# SCH_TWINKLING_CHRISMATIS_LIGHT_2023-04-2.net
KiCad netlist of a schematic drawn in EasyEDA
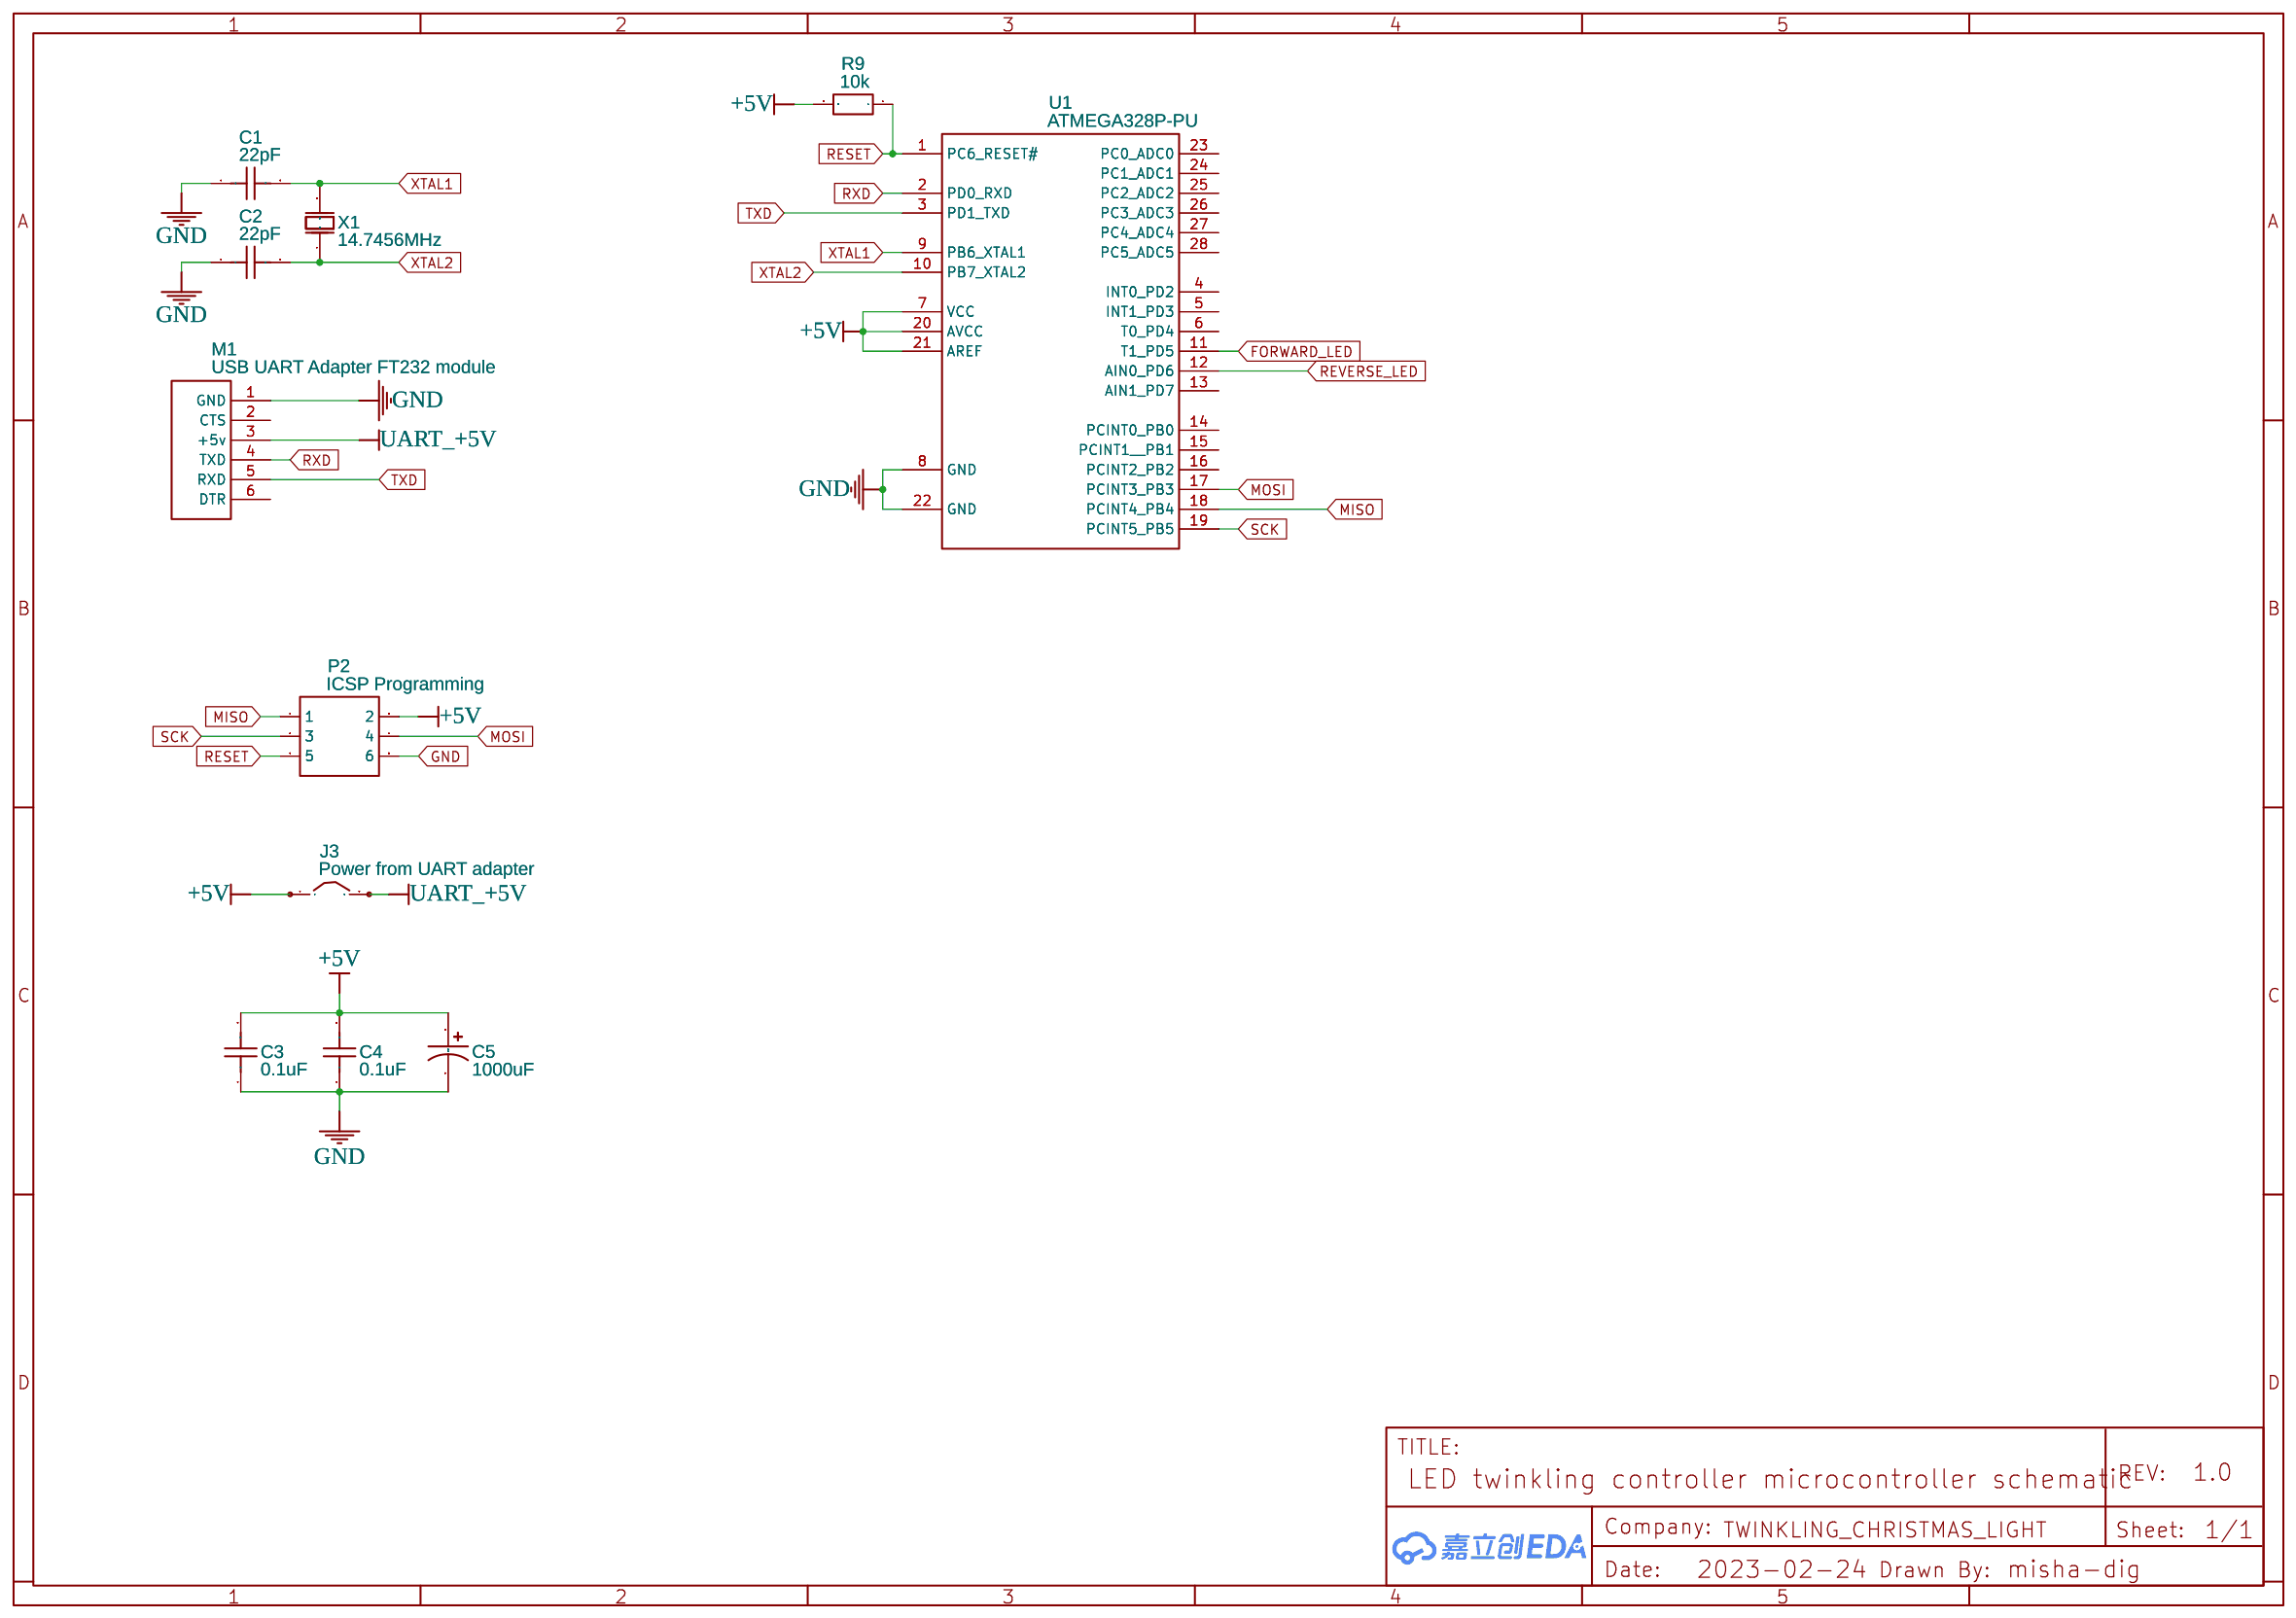
[diagram p0: MAIN_SCHEMATIC_TWINKLING_CHRISTMAS_LIGHT]
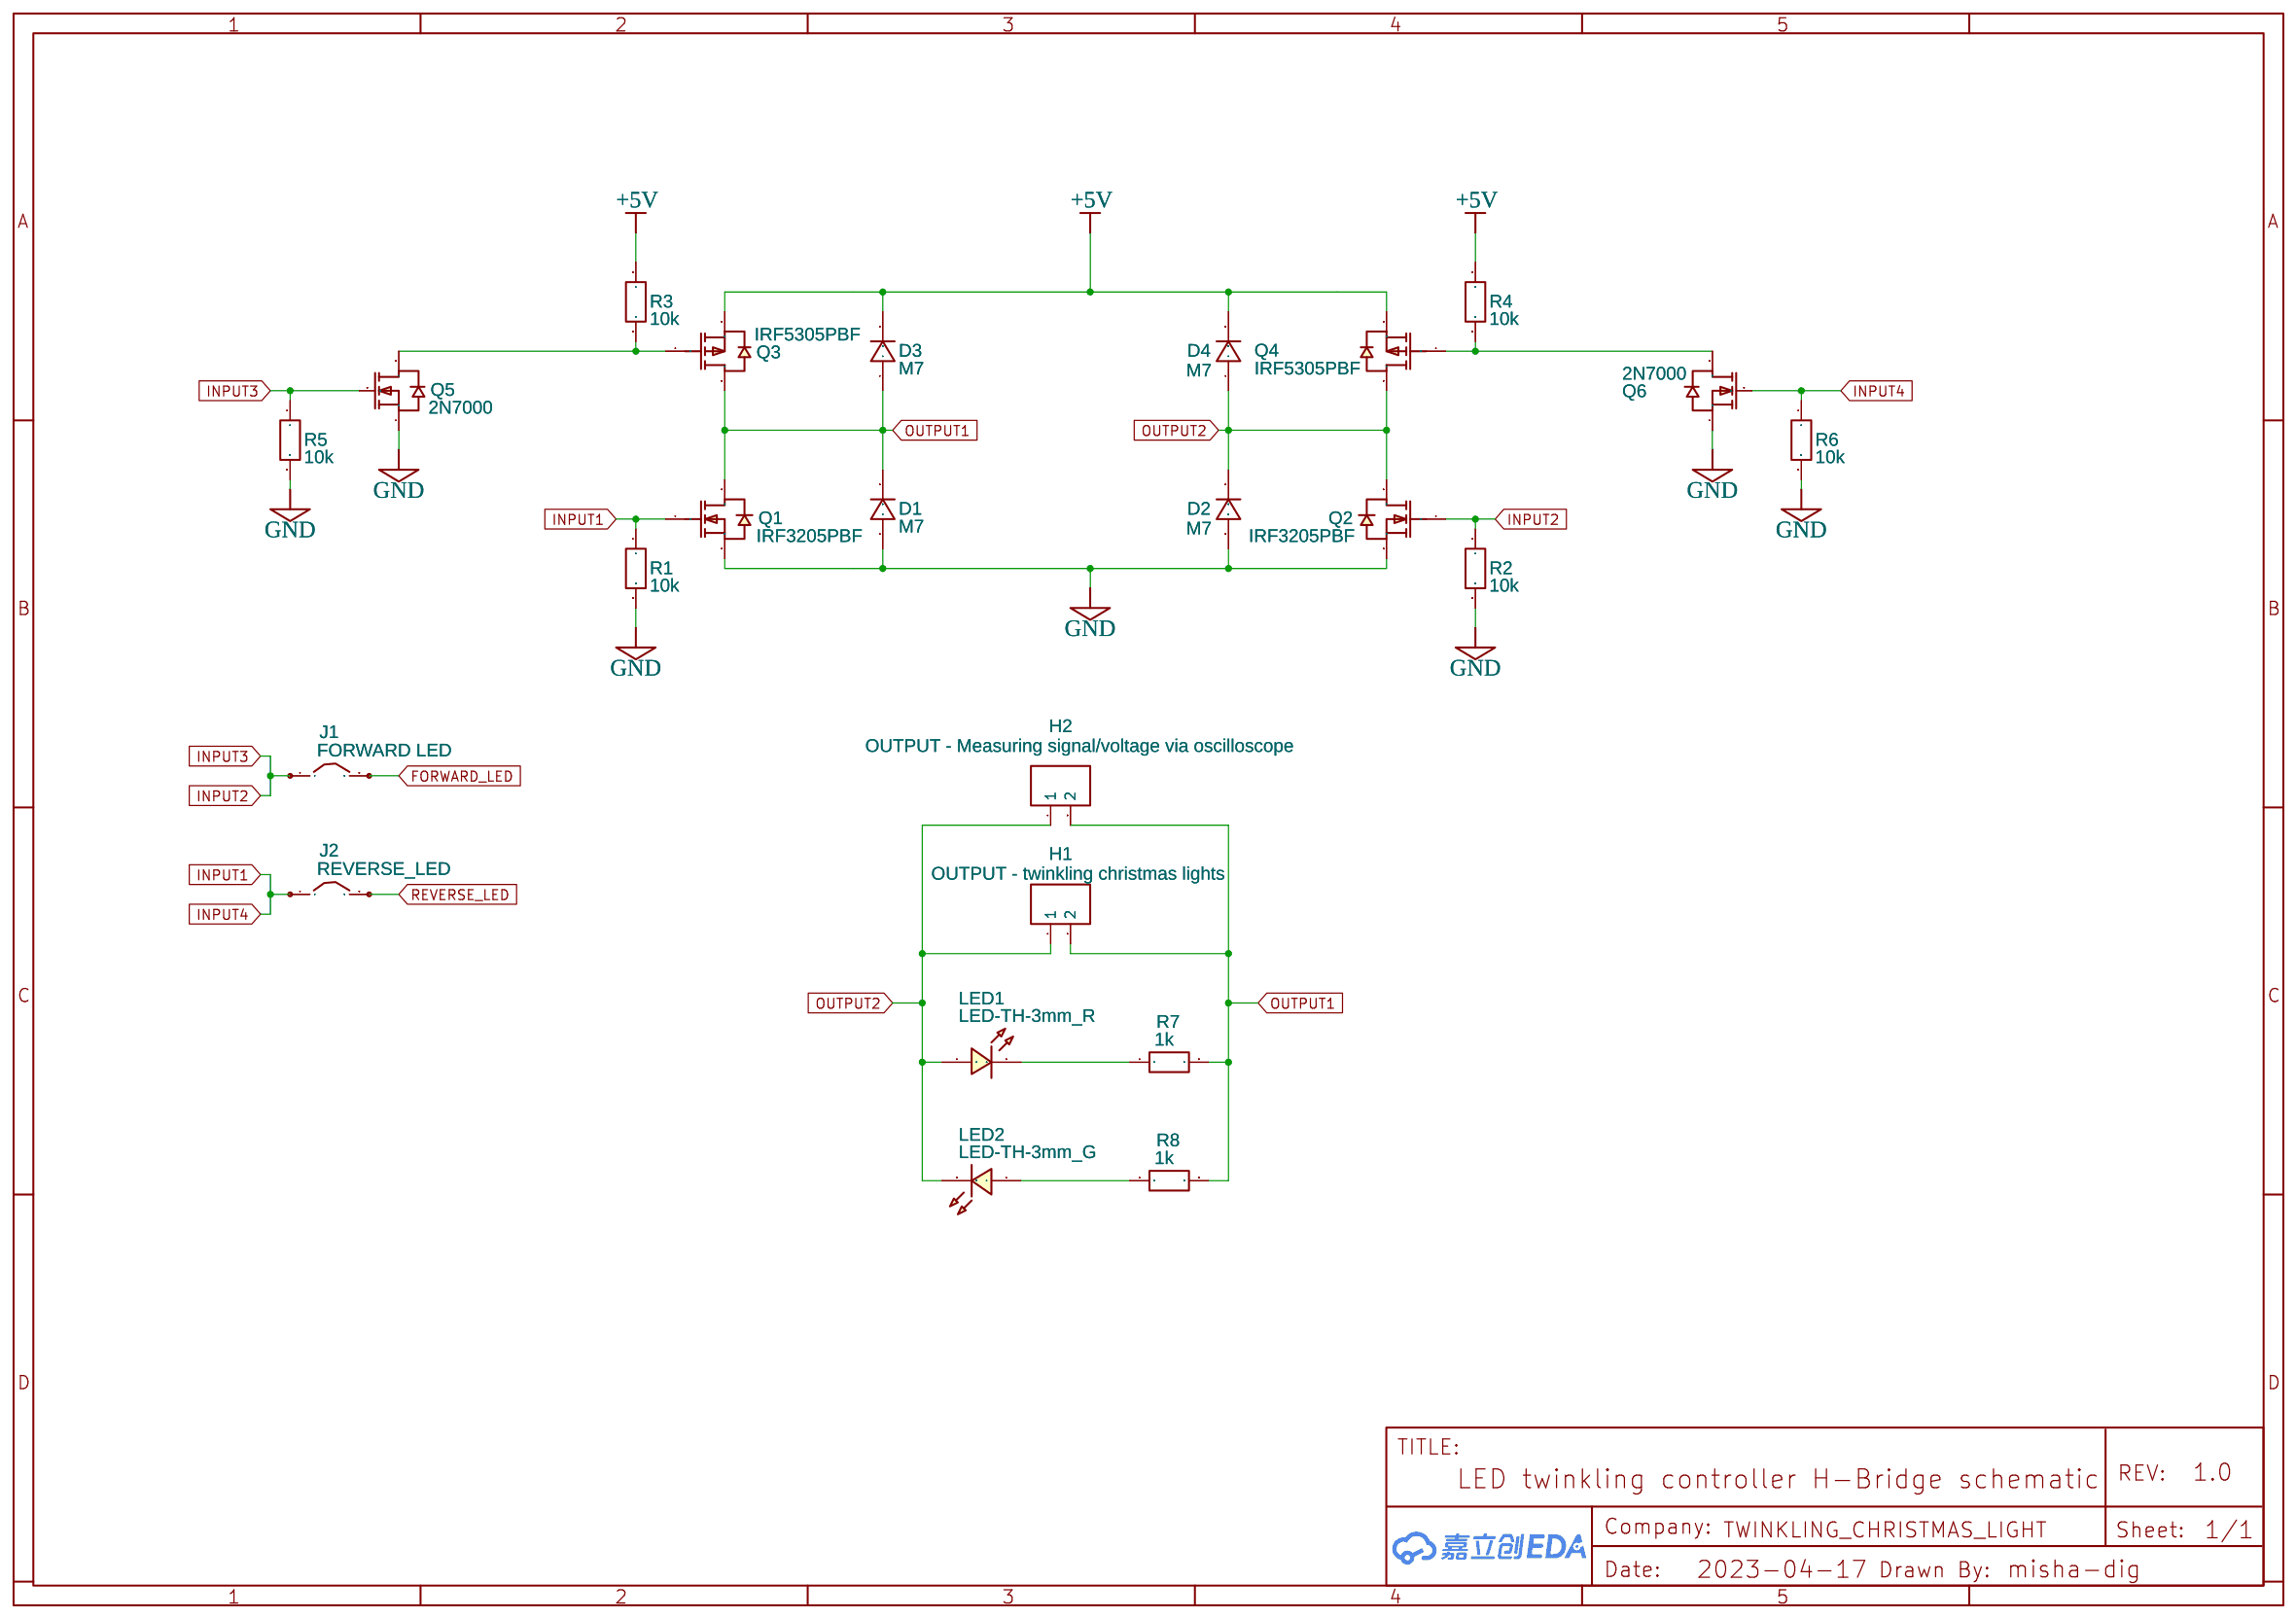
[diagram p1: H-BRIDGE_SCHEMATIC_TWINKLING_CHRISTMAS_LIGHT]

(export (version "E")
  (design (tool "Eeschema 10.0.6"))
  (components
    (comp (ref "C1") (value "22pF") (libsource (lib "") (part "C_0805_US")))
    (comp (ref "C2") (value "22pF") (libsource (lib "") (part "C_0805_US")))
    (comp (ref "C3") (value "0.1uF") (libsource (lib "") (part "C_0805_US_1")))
    (comp (ref "C4") (value "0.1uF") (libsource (lib "") (part "C_0805_US_1")))
    (comp (ref "C5") (value "1000uF") (libsource (lib "") (part "CE_TH_D8.0×F3.5_US")))
    (comp (ref "J3")
      (value "Power from UART adapter")
      (fields (field (name "BOM_Manufacturer Part") "NONE"))
      (libsource (lib "") (part "JUMPERTHRUHOLE"))
    )
    (comp (ref "M1") (value "USB UART Adapter FT232 module") (libsource (lib "") (part "FT232UART_HEADER")))
    (comp (ref "P2")
      (value "ICSP Programming")
      (fields
        (field (name "BOM_Manufacturer Part") "2X3 2.54mm IDC Box")
        (field (name "BOM_Supplier Part") "C11214")
      )
      (libsource (lib "") (part "HDR-IDC-2.54-2X3P"))
    )
    (comp (ref "R9") (value "10k") (libsource (lib "") (part "R_0805_EU")))
    (comp (ref "U1")
      (value "ATMEGA328P-PU")
      (fields (field (name "BOM_Supplier Part") "C33901"))
      (libsource (lib "") (part "ATMEGA328P-PU"))
    )
    (comp (ref "X1")
      (value "14.7456MHz")
      (fields
        (field (name "BOM_Manufacturer Part") "ECS-147.4-S-1X")
        (field (name "BOM_Supplier Part") "C2636393")
      )
      (libsource (lib "") (part "ECS-147.4-S-1X"))
    )
    (comp (ref "D1")
      (value "M7")
      (fields (field (name "BOM_Manufacturer Part") "1N4007") (field (name "BOM_Supplier Part") "C126233"))
      (libsource (lib "") (part "M7"))
    )
    (comp (ref "D2")
      (value "M7")
      (fields (field (name "BOM_Manufacturer Part") "1N4007") (field (name "BOM_Supplier Part") "C126233"))
      (libsource (lib "") (part "M7"))
    )
    (comp (ref "D3")
      (value "M7")
      (fields (field (name "BOM_Manufacturer Part") "1N4007") (field (name "BOM_Supplier Part") "C126233"))
      (libsource (lib "") (part "M7"))
    )
    (comp (ref "D4")
      (value "M7")
      (fields (field (name "BOM_Manufacturer Part") "1N4007") (field (name "BOM_Supplier Part") "C126233"))
      (libsource (lib "") (part "M7"))
    )
    (comp (ref "H1")
      (value "OUTPUT - twinkling christmas lights")
      (fields (field (name "BOM_Supplier Part") "C49661"))
      (libsource (lib "") (part "HDR-F-2.54_1x2"))
    )
    (comp (ref "H2")
      (value "OUTPUT - Measuring signal/voltage via oscilloscope")
      (fields (field (name "BOM_Supplier Part") "C49661"))
      (libsource (lib "") (part "HDR-F-2.54_1x2"))
    )
    (comp (ref "J1")
      (value "FORWARD LED")
      (fields (field (name "BOM_Manufacturer Part") "NONE"))
      (libsource (lib "") (part "JUMPERTHRUHOLE"))
    )
    (comp (ref "J2")
      (value "REVERSE_LED")
      (fields (field (name "BOM_Manufacturer Part") "NONE"))
      (libsource (lib "") (part "JUMPERTHRUHOLE"))
    )
    (comp (ref "LED1")
      (value "LED-TH-3mm_R")
      (fields
        (field (name "BOM_Manufacturer Part") "204-10SDRD/S530-A3-L")
        (field (name "BOM_Supplier Part") "C84774")
      )
      (libsource (lib "") (part "LED-TH-3mm_R"))
    )
    (comp (ref "LED2")
      (value "LED-TH-3mm_G")
      (fields
        (field (name "BOM_Manufacturer Part") "204-10SYGD/S530-E3")
        (field (name "BOM_Supplier Part") "C85161")
      )
      (libsource (lib "") (part "LED-TH-3mm_G"))
    )
    (comp (ref "Q1")
      (value "IRF3205PBF")
      (fields (field (name "BOM_Supplier Part") "C2561"))
      (libsource (lib "") (part "IRF3205PBF"))
    )
    (comp (ref "Q2")
      (value "IRF3205PBF")
      (fields (field (name "BOM_Supplier Part") "C2561"))
      (libsource (lib "") (part "IRF3205PBF_1"))
    )
    (comp (ref "Q3")
      (value "IRF5305PBF")
      (fields (field (name "BOM_Supplier Part") "C2623"))
      (libsource (lib "") (part "IRF5305PBF_1"))
    )
    (comp (ref "Q4")
      (value "IRF5305PBF")
      (fields (field (name "BOM_Supplier Part") "C2623"))
      (libsource (lib "") (part "IRF5305PBF"))
    )
    (comp (ref "Q5")
      (value "2N7000")
      (fields (field (name "BOM_Supplier Part") "C9114"))
      (libsource (lib "") (part "2N7000"))
    )
    (comp (ref "Q6")
      (value "2N7000")
      (fields (field (name "BOM_Supplier Part") "C9114"))
      (libsource (lib "") (part "2N7000_1"))
    )
    (comp (ref "R1") (value "10k") (libsource (lib "") (part "R_AXIAL-0.6_EU_1")))
    (comp (ref "R2") (value "10k") (libsource (lib "") (part "R_AXIAL-0.6_EU_1")))
    (comp (ref "R3") (value "10k") (libsource (lib "") (part "R_AXIAL-0.6_EU_1")))
    (comp (ref "R4") (value "10k") (libsource (lib "") (part "R_AXIAL-0.6_EU_1")))
    (comp (ref "R5") (value "10k") (libsource (lib "") (part "R_AXIAL-0.6_EU_1")))
    (comp (ref "R6") (value "10k") (libsource (lib "") (part "R_AXIAL-0.6_EU_1")))
    (comp (ref "R7") (value "1k") (libsource (lib "") (part "R_AXIAL-0.6_EU")))
    (comp (ref "R8") (value "1k") (libsource (lib "") (part "R_AXIAL-0.6_EU")))
  )
  (nets
    (net (code "1") (name "+5V") (class "Default")
      (node (ref "C3") (pin "2") (pinfunction "2_2") (pintype "unspecified"))
      (node (ref "C4") (pin "2") (pinfunction "2_2") (pintype "unspecified"))
      (node (ref "C5") (pin "1") (pinfunction "1_1") (pintype "unspecified"))
      (node (ref "D3") (pin "2") (pinfunction "2_2") (pintype "unspecified"))
      (node (ref "D4") (pin "2") (pinfunction "2_2") (pintype "unspecified"))
      (node (ref "J3") (pin "1") (pinfunction "1_1") (pintype "unspecified"))
      (node (ref "P2") (pin "2") (pinfunction "2_2") (pintype "unspecified"))
      (node (ref "Q3") (pin "3") (pinfunction "S_3") (pintype "unspecified"))
      (node (ref "Q4") (pin "3") (pinfunction "S_3") (pintype "unspecified"))
      (node (ref "R3") (pin "1") (pinfunction "1_1") (pintype "unspecified"))
      (node (ref "R4") (pin "1") (pinfunction "1_1") (pintype "unspecified"))
      (node (ref "R9") (pin "2") (pinfunction "2_2") (pintype "unspecified"))
      (node (ref "U1") (pin "20") (pinfunction "AVCC_20") (pintype "passive"))
      (node (ref "U1") (pin "21") (pinfunction "AREF_21") (pintype "passive"))
      (node (ref "U1") (pin "7") (pinfunction "VCC_7") (pintype "passive"))
    )
    (net (code "2") (name "FORWARD_LED") (class "Default")
      (node (ref "J1") (pin "2") (pinfunction "2_2") (pintype "unspecified"))
      (node (ref "U1") (pin "11") (pinfunction "T1_PD5_11") (pintype "bidirectional"))
    )
    (net (code "3") (name "GND") (class "Default")
      (node (ref "C1") (pin "1") (pinfunction "1_1") (pintype "unspecified"))
      (node (ref "C2") (pin "1") (pinfunction "1_1") (pintype "unspecified"))
      (node (ref "C3") (pin "1") (pinfunction "1_1") (pintype "unspecified"))
      (node (ref "C4") (pin "1") (pinfunction "1_1") (pintype "unspecified"))
      (node (ref "C5") (pin "2") (pinfunction "2_2") (pintype "unspecified"))
      (node (ref "D1") (pin "1") (pinfunction "1_1") (pintype "unspecified"))
      (node (ref "D2") (pin "1") (pinfunction "1_1") (pintype "unspecified"))
      (node (ref "M1") (pin "1") (pinfunction "GND_1") (pintype "unspecified"))
      (node (ref "P2") (pin "6") (pinfunction "6_6") (pintype "unspecified"))
      (node (ref "Q1") (pin "3") (pinfunction "S_3") (pintype "unspecified"))
      (node (ref "Q2") (pin "3") (pinfunction "S_3") (pintype "unspecified"))
      (node (ref "Q5") (pin "1") (pinfunction "S_1") (pintype "unspecified"))
      (node (ref "Q6") (pin "1") (pinfunction "S_1") (pintype "unspecified"))
      (node (ref "R1") (pin "2") (pinfunction "2_2") (pintype "unspecified"))
      (node (ref "R2") (pin "2") (pinfunction "2_2") (pintype "unspecified"))
      (node (ref "R5") (pin "2") (pinfunction "2_2") (pintype "unspecified"))
      (node (ref "R6") (pin "2") (pinfunction "2_2") (pintype "unspecified"))
      (node (ref "U1") (pin "22") (pinfunction "GND_22") (pintype "passive"))
      (node (ref "U1") (pin "8") (pinfunction "GND_8") (pintype "passive"))
    )
    (net (code "4") (name "INPUT1") (class "Default")
      (node (ref "J2") (pin "1") (pinfunction "1_1") (pintype "unspecified"))
      (node (ref "Q1") (pin "1") (pinfunction "G_1") (pintype "unspecified"))
      (node (ref "Q6") (pin "2") (pinfunction "G_2") (pintype "unspecified"))
      (node (ref "R1") (pin "1") (pinfunction "1_1") (pintype "unspecified"))
      (node (ref "R6") (pin "1") (pinfunction "1_1") (pintype "unspecified"))
    )
    (net (code "5") (name "INPUT2") (class "Default")
      (node (ref "J1") (pin "1") (pinfunction "1_1") (pintype "unspecified"))
      (node (ref "Q2") (pin "1") (pinfunction "G_1") (pintype "unspecified"))
      (node (ref "Q5") (pin "2") (pinfunction "G_2") (pintype "unspecified"))
      (node (ref "R2") (pin "1") (pinfunction "1_1") (pintype "unspecified"))
      (node (ref "R5") (pin "1") (pinfunction "1_1") (pintype "unspecified"))
    )
    (net (code "6") (name "MISO") (class "Default")
      (node (ref "P2") (pin "1") (pinfunction "1_1") (pintype "unspecified"))
      (node (ref "U1") (pin "18") (pinfunction "PCINT4_PB4_18") (pintype "bidirectional"))
    )
    (net (code "7") (name "MOSI") (class "Default")
      (node (ref "P2") (pin "4") (pinfunction "4_4") (pintype "unspecified"))
      (node (ref "U1") (pin "17") (pinfunction "PCINT3_PB3_17") (pintype "bidirectional"))
    )
    (net (code "8") (name "Net-(LED1-Pad2)") (class "Default")
      (node (ref "LED1") (pin "2") (pinfunction "2_2") (pintype "unspecified"))
      (node (ref "R7") (pin "1") (pinfunction "1_1") (pintype "unspecified"))
    )
    (net (code "9") (name "Net-(LED2-Pad1)") (class "Default")
      (node (ref "LED2") (pin "1") (pinfunction "1_1") (pintype "unspecified"))
      (node (ref "R8") (pin "1") (pinfunction "1_1") (pintype "unspecified"))
    )
    (net (code "10") (name "Net-(Q3-G)") (class "Default")
      (node (ref "Q3") (pin "1") (pinfunction "G_1") (pintype "unspecified"))
      (node (ref "Q5") (pin "3") (pinfunction "D_3") (pintype "unspecified"))
      (node (ref "R3") (pin "2") (pinfunction "2_2") (pintype "unspecified"))
    )
    (net (code "11") (name "Net-(Q4-G)") (class "Default")
      (node (ref "Q4") (pin "1") (pinfunction "G_1") (pintype "unspecified"))
      (node (ref "Q6") (pin "3") (pinfunction "D_3") (pintype "unspecified"))
      (node (ref "R4") (pin "2") (pinfunction "2_2") (pintype "unspecified"))
    )
    (net (code "12") (name "OUTPUT1") (class "Default")
      (node (ref "D1") (pin "2") (pinfunction "2_2") (pintype "unspecified"))
      (node (ref "D3") (pin "1") (pinfunction "1_1") (pintype "unspecified"))
      (node (ref "H1") (pin "2") (pinfunction "2_2") (pintype "input"))
      (node (ref "H2") (pin "2") (pinfunction "2_2") (pintype "input"))
      (node (ref "Q1") (pin "2") (pinfunction "D_2") (pintype "unspecified"))
      (node (ref "Q3") (pin "2") (pinfunction "D_2") (pintype "unspecified"))
      (node (ref "R7") (pin "2") (pinfunction "2_2") (pintype "unspecified"))
      (node (ref "R8") (pin "2") (pinfunction "2_2") (pintype "unspecified"))
    )
    (net (code "13") (name "OUTPUT2") (class "Default")
      (node (ref "D2") (pin "2") (pinfunction "2_2") (pintype "unspecified"))
      (node (ref "D4") (pin "1") (pinfunction "1_1") (pintype "unspecified"))
      (node (ref "H1") (pin "1") (pinfunction "1_1") (pintype "input"))
      (node (ref "H2") (pin "1") (pinfunction "1_1") (pintype "input"))
      (node (ref "LED1") (pin "1") (pinfunction "1_1") (pintype "unspecified"))
      (node (ref "LED2") (pin "2") (pinfunction "2_2") (pintype "unspecified"))
      (node (ref "Q2") (pin "2") (pinfunction "D_2") (pintype "unspecified"))
      (node (ref "Q4") (pin "2") (pinfunction "D_2") (pintype "unspecified"))
    )
    (net (code "14") (name "RESET") (class "Default")
      (node (ref "P2") (pin "5") (pinfunction "5_5") (pintype "unspecified"))
      (node (ref "R9") (pin "1") (pinfunction "1_1") (pintype "unspecified"))
      (node (ref "U1") (pin "1") (pinfunction "PC6_RESET#_1") (pintype "bidirectional"))
    )
    (net (code "15") (name "REVERSE_LED") (class "Default")
      (node (ref "J2") (pin "2") (pinfunction "2_2") (pintype "unspecified"))
      (node (ref "U1") (pin "12") (pinfunction "AIN0_PD6_12") (pintype "bidirectional"))
    )
    (net (code "16") (name "RXD") (class "Default")
      (node (ref "M1") (pin "4") (pinfunction "TXD_4") (pintype "unspecified"))
      (node (ref "U1") (pin "2") (pinfunction "PD0_RXD_2") (pintype "bidirectional"))
    )
    (net (code "17") (name "SCK") (class "Default")
      (node (ref "P2") (pin "3") (pinfunction "3_3") (pintype "unspecified"))
      (node (ref "U1") (pin "19") (pinfunction "PCINT5_PB5_19") (pintype "bidirectional"))
    )
    (net (code "18") (name "TXD") (class "Default")
      (node (ref "M1") (pin "5") (pinfunction "RXD_5") (pintype "unspecified"))
      (node (ref "U1") (pin "3") (pinfunction "PD1_TXD_3") (pintype "bidirectional"))
    )
    (net (code "19") (name "UART_+5V") (class "Default")
      (node (ref "J3") (pin "2") (pinfunction "2_2") (pintype "unspecified"))
      (node (ref "M1") (pin "3") (pinfunction "+5v_3") (pintype "unspecified"))
    )
    (net (code "20") (name "XTAL1") (class "Default")
      (node (ref "C1") (pin "2") (pinfunction "2_2") (pintype "unspecified"))
      (node (ref "U1") (pin "9") (pinfunction "PB6_XTAL1_9") (pintype "bidirectional"))
      (node (ref "X1") (pin "2") (pinfunction "OSC2_2") (pintype "input"))
    )
    (net (code "21") (name "XTAL2") (class "Default")
      (node (ref "C2") (pin "2") (pinfunction "2_2") (pintype "unspecified"))
      (node (ref "U1") (pin "10") (pinfunction "PB7_XTAL2_10") (pintype "bidirectional"))
      (node (ref "X1") (pin "1") (pinfunction "OSC1_1") (pintype "input"))
    )
    (net (code "22") (name "unconnected-(M1-CTS-Pad2)") (class "Default")
      (node (ref "M1") (pin "2") (pinfunction "CTS_2") (pintype "unspecified"))
    )
    (net (code "23") (name "unconnected-(M1-DTR-Pad6)") (class "Default")
      (node (ref "M1") (pin "6") (pinfunction "DTR_6") (pintype "unspecified"))
    )
    (net (code "24") (name "unconnected-(U1-AIN1_PD7-Pad13)") (class "Default")
      (node (ref "U1") (pin "13") (pinfunction "AIN1_PD7_13") (pintype "bidirectional"))
    )
    (net (code "25") (name "unconnected-(U1-INT0_PD2-Pad4)") (class "Default")
      (node (ref "U1") (pin "4") (pinfunction "INT0_PD2_4") (pintype "bidirectional"))
    )
    (net (code "26") (name "unconnected-(U1-INT1_PD3-Pad5)") (class "Default")
      (node (ref "U1") (pin "5") (pinfunction "INT1_PD3_5") (pintype "bidirectional"))
    )
    (net (code "27") (name "unconnected-(U1-PC0_ADC0-Pad23)") (class "Default")
      (node (ref "U1") (pin "23") (pinfunction "PC0_ADC0_23") (pintype "bidirectional"))
    )
    (net (code "28") (name "unconnected-(U1-PC1_ADC1-Pad24)") (class "Default")
      (node (ref "U1") (pin "24") (pinfunction "PC1_ADC1_24") (pintype "bidirectional"))
    )
    (net (code "29") (name "unconnected-(U1-PC2_ADC2-Pad25)") (class "Default")
      (node (ref "U1") (pin "25") (pinfunction "PC2_ADC2_25") (pintype "bidirectional"))
    )
    (net (code "30") (name "unconnected-(U1-PC3_ADC3-Pad26)") (class "Default")
      (node (ref "U1") (pin "26") (pinfunction "PC3_ADC3_26") (pintype "bidirectional"))
    )
    (net (code "31") (name "unconnected-(U1-PC4_ADC4-Pad27)") (class "Default")
      (node (ref "U1") (pin "27") (pinfunction "PC4_ADC4_27") (pintype "bidirectional"))
    )
    (net (code "32") (name "unconnected-(U1-PC5_ADC5-Pad28)") (class "Default")
      (node (ref "U1") (pin "28") (pinfunction "PC5_ADC5_28") (pintype "bidirectional"))
    )
    (net (code "33") (name "unconnected-(U1-PCINT0_PB0-Pad14)") (class "Default")
      (node (ref "U1") (pin "14") (pinfunction "PCINT0_PB0_14") (pintype "bidirectional"))
    )
    (net (code "34") (name "unconnected-(U1-PCINT1__PB1-Pad15)") (class "Default")
      (node (ref "U1") (pin "15") (pinfunction "PCINT1__PB1_15") (pintype "bidirectional"))
    )
    (net (code "35") (name "unconnected-(U1-PCINT2_PB2-Pad16)") (class "Default")
      (node (ref "U1") (pin "16") (pinfunction "PCINT2_PB2_16") (pintype "bidirectional"))
    )
    (net (code "36") (name "unconnected-(U1-T0_PD4-Pad6)") (class "Default")
      (node (ref "U1") (pin "6") (pinfunction "T0_PD4_6") (pintype "bidirectional"))
    )
  )
)
